# ET2_test_Chip_V1.net
KiCad netlist of a schematic drawn in Altium Designer
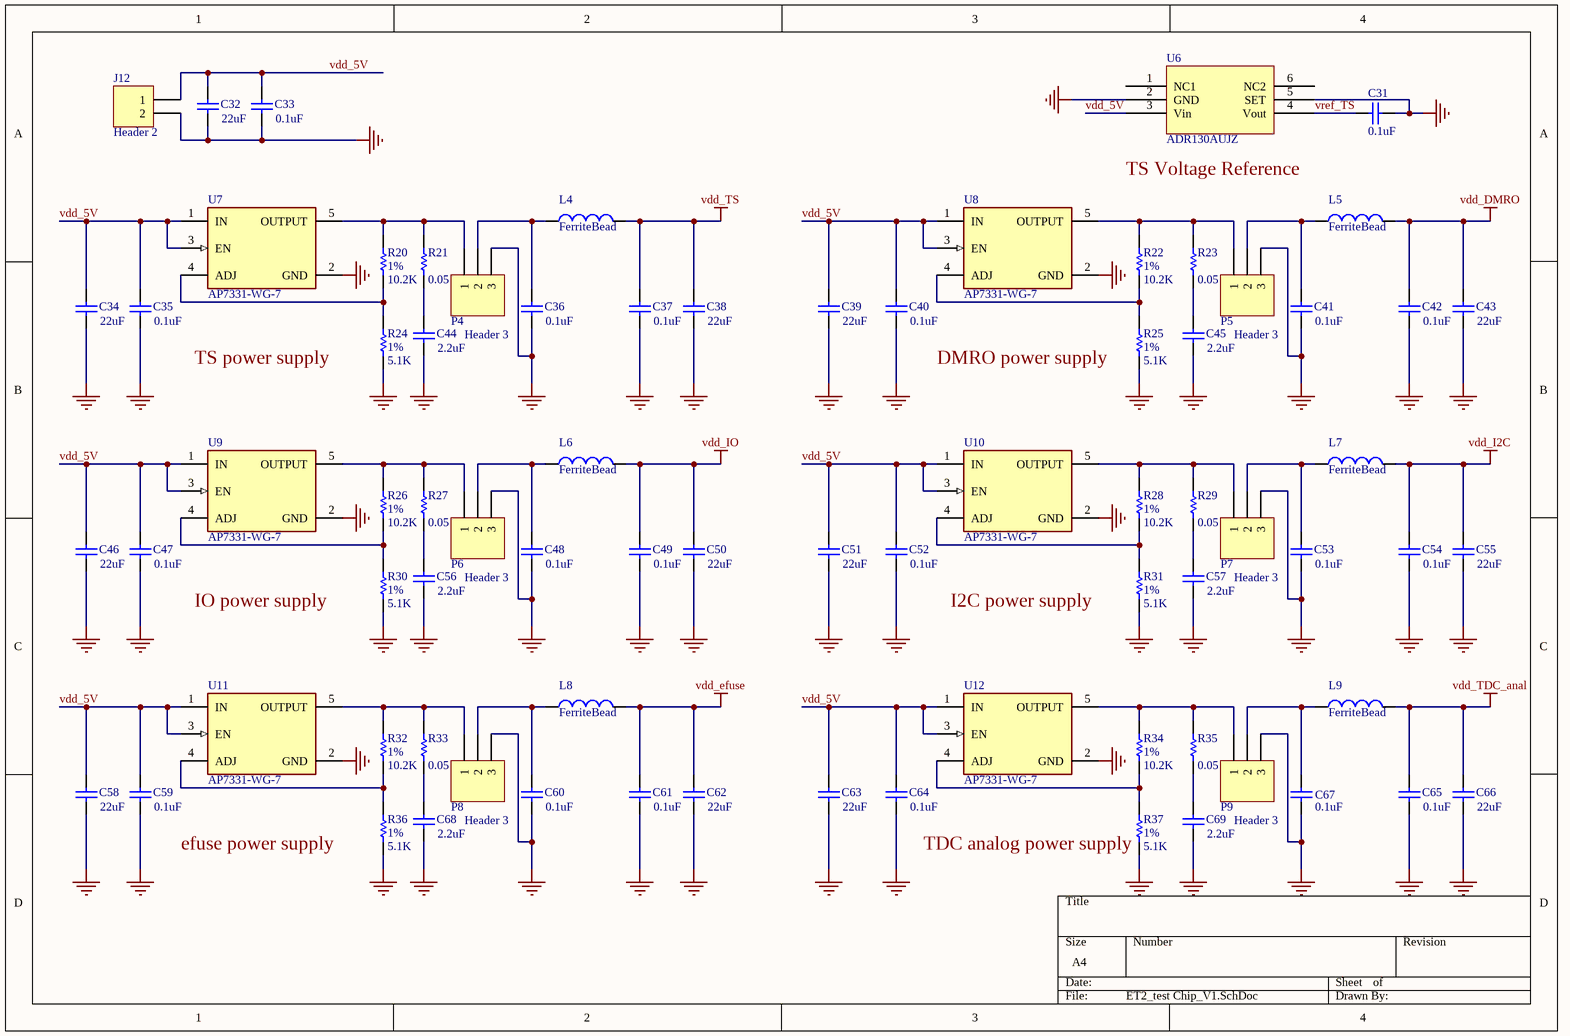
[diagram p0: ET2_test Chip_V1.SchDoc]

(export (version "E")
  (design (tool "Eeschema 10.0.6"))
  (components
    (comp (ref "C31")
      (value "0.1uF")
      (footprint "0402-eagle")
      (description "Capacitor")
      (fields (field (name "Comment") "Cap") (field (name "PUBLISHER") "Altium Limited"))
      (libsource (lib "Miscellaneous Devices") (part "Cap"))
    )
    (comp (ref "C32")
      (value "22uF")
      (footprint "C1210")
      (description "Capacitor")
      (fields (field (name "Comment") "Cap") (field (name "PUBLISHER") "Altium Limited"))
      (libsource (lib "Miscellaneous Devices") (part "Cap"))
    )
    (comp (ref "C33")
      (value "0.1uF")
      (footprint "0805-eagle")
      (description "Capacitor")
      (fields (field (name "Comment") "Cap") (field (name "PUBLISHER") "Altium Limited"))
      (libsource (lib "Miscellaneous Devices") (part "Cap"))
    )
    (comp (ref "C34")
      (value "22uF")
      (footprint "C1210")
      (description "Capacitor")
      (fields (field (name "Comment") "Cap") (field (name "PUBLISHER") "Altium Limited"))
      (libsource (lib "Miscellaneous Devices") (part "Cap"))
    )
    (comp (ref "C35")
      (value "0.1uF")
      (footprint "0805-eagle")
      (description "Capacitor")
      (fields (field (name "Comment") "Cap") (field (name "PUBLISHER") "Altium Limited"))
      (libsource (lib "Miscellaneous Devices") (part "Cap"))
    )
    (comp (ref "C36")
      (value "0.1uF")
      (footprint "0805-eagle")
      (description "Capacitor")
      (fields (field (name "Comment") "Cap") (field (name "PUBLISHER") "Altium Limited"))
      (libsource (lib "Miscellaneous Devices") (part "Cap"))
    )
    (comp (ref "C37")
      (value "0.1uF")
      (footprint "0805-eagle")
      (description "Capacitor")
      (fields (field (name "Comment") "Cap") (field (name "PUBLISHER") "Altium Limited"))
      (libsource (lib "Miscellaneous Devices") (part "Cap"))
    )
    (comp (ref "C38")
      (value "22uF")
      (footprint "C1210")
      (description "Capacitor")
      (fields (field (name "Comment") "Cap") (field (name "PUBLISHER") "Altium Limited"))
      (libsource (lib "Miscellaneous Devices") (part "Cap"))
    )
    (comp (ref "C39")
      (value "22uF")
      (footprint "C1210")
      (description "Capacitor")
      (fields (field (name "Comment") "Cap") (field (name "PUBLISHER") "Altium Limited"))
      (libsource (lib "Miscellaneous Devices") (part "Cap"))
    )
    (comp (ref "C40")
      (value "0.1uF")
      (footprint "0805-eagle")
      (description "Capacitor")
      (fields (field (name "Comment") "Cap") (field (name "PUBLISHER") "Altium Limited"))
      (libsource (lib "Miscellaneous Devices") (part "Cap"))
    )
    (comp (ref "C41")
      (value "0.1uF")
      (footprint "0805-eagle")
      (description "Capacitor")
      (fields (field (name "Comment") "Cap") (field (name "PUBLISHER") "Altium Limited"))
      (libsource (lib "Miscellaneous Devices") (part "Cap"))
    )
    (comp (ref "C42")
      (value "0.1uF")
      (footprint "0805-eagle")
      (description "Capacitor")
      (fields (field (name "Comment") "Cap") (field (name "PUBLISHER") "Altium Limited"))
      (libsource (lib "Miscellaneous Devices") (part "Cap"))
    )
    (comp (ref "C43")
      (value "22uF")
      (footprint "C1210")
      (description "Capacitor")
      (fields (field (name "Comment") "Cap") (field (name "PUBLISHER") "Altium Limited"))
      (libsource (lib "Miscellaneous Devices") (part "Cap"))
    )
    (comp (ref "C44")
      (value "2.2uF")
      (footprint "0805-eagle")
      (description "Capacitor")
      (fields (field (name "Comment") "Cap") (field (name "PUBLISHER") "Altium Limited"))
      (libsource (lib "Miscellaneous Devices") (part "Cap"))
    )
    (comp (ref "C45")
      (value "2.2uF")
      (footprint "0805-eagle")
      (description "Capacitor")
      (fields (field (name "Comment") "Cap") (field (name "PUBLISHER") "Altium Limited"))
      (libsource (lib "Miscellaneous Devices") (part "Cap"))
    )
    (comp (ref "C46")
      (value "22uF")
      (footprint "C1210")
      (description "Capacitor")
      (fields (field (name "Comment") "Cap") (field (name "PUBLISHER") "Altium Limited"))
      (libsource (lib "Miscellaneous Devices") (part "Cap"))
    )
    (comp (ref "C47")
      (value "0.1uF")
      (footprint "0805-eagle")
      (description "Capacitor")
      (fields (field (name "Comment") "Cap") (field (name "PUBLISHER") "Altium Limited"))
      (libsource (lib "Miscellaneous Devices") (part "Cap"))
    )
    (comp (ref "C48")
      (value "0.1uF")
      (footprint "0805-eagle")
      (description "Capacitor")
      (fields (field (name "Comment") "Cap") (field (name "PUBLISHER") "Altium Limited"))
      (libsource (lib "Miscellaneous Devices") (part "Cap"))
    )
    (comp (ref "C49")
      (value "0.1uF")
      (footprint "0805-eagle")
      (description "Capacitor")
      (fields (field (name "Comment") "Cap") (field (name "PUBLISHER") "Altium Limited"))
      (libsource (lib "Miscellaneous Devices") (part "Cap"))
    )
    (comp (ref "C50")
      (value "22uF")
      (footprint "C1210")
      (description "Capacitor")
      (fields (field (name "Comment") "Cap") (field (name "PUBLISHER") "Altium Limited"))
      (libsource (lib "Miscellaneous Devices") (part "Cap"))
    )
    (comp (ref "C51")
      (value "22uF")
      (footprint "C1210")
      (description "Capacitor")
      (fields (field (name "Comment") "Cap") (field (name "PUBLISHER") "Altium Limited"))
      (libsource (lib "Miscellaneous Devices") (part "Cap"))
    )
    (comp (ref "C52")
      (value "0.1uF")
      (footprint "0805-eagle")
      (description "Capacitor")
      (fields (field (name "Comment") "Cap") (field (name "PUBLISHER") "Altium Limited"))
      (libsource (lib "Miscellaneous Devices") (part "Cap"))
    )
    (comp (ref "C53")
      (value "0.1uF")
      (footprint "0805-eagle")
      (description "Capacitor")
      (fields (field (name "Comment") "Cap") (field (name "PUBLISHER") "Altium Limited"))
      (libsource (lib "Miscellaneous Devices") (part "Cap"))
    )
    (comp (ref "C54")
      (value "0.1uF")
      (footprint "0805-eagle")
      (description "Capacitor")
      (fields (field (name "Comment") "Cap") (field (name "PUBLISHER") "Altium Limited"))
      (libsource (lib "Miscellaneous Devices") (part "Cap"))
    )
    (comp (ref "C55")
      (value "22uF")
      (footprint "C1210")
      (description "Capacitor")
      (fields (field (name "Comment") "Cap") (field (name "PUBLISHER") "Altium Limited"))
      (libsource (lib "Miscellaneous Devices") (part "Cap"))
    )
    (comp (ref "C56")
      (value "2.2uF")
      (footprint "0805-eagle")
      (description "Capacitor")
      (fields (field (name "Comment") "Cap") (field (name "PUBLISHER") "Altium Limited"))
      (libsource (lib "Miscellaneous Devices") (part "Cap"))
    )
    (comp (ref "C57")
      (value "2.2uF")
      (footprint "0805-eagle")
      (description "Capacitor")
      (fields (field (name "Comment") "Cap") (field (name "PUBLISHER") "Altium Limited"))
      (libsource (lib "Miscellaneous Devices") (part "Cap"))
    )
    (comp (ref "C58")
      (value "22uF")
      (footprint "C1210")
      (description "Capacitor")
      (fields (field (name "Comment") "Cap") (field (name "PUBLISHER") "Altium Limited"))
      (libsource (lib "Miscellaneous Devices") (part "Cap"))
    )
    (comp (ref "C59")
      (value "0.1uF")
      (footprint "0805-eagle")
      (description "Capacitor")
      (fields (field (name "Comment") "Cap") (field (name "PUBLISHER") "Altium Limited"))
      (libsource (lib "Miscellaneous Devices") (part "Cap"))
    )
    (comp (ref "C60")
      (value "0.1uF")
      (footprint "0805-eagle")
      (description "Capacitor")
      (fields (field (name "Comment") "Cap") (field (name "PUBLISHER") "Altium Limited"))
      (libsource (lib "Miscellaneous Devices") (part "Cap"))
    )
    (comp (ref "C61")
      (value "0.1uF")
      (footprint "0805-eagle")
      (description "Capacitor")
      (fields (field (name "Comment") "Cap") (field (name "PUBLISHER") "Altium Limited"))
      (libsource (lib "Miscellaneous Devices") (part "Cap"))
    )
    (comp (ref "C62")
      (value "22uF")
      (footprint "C1210")
      (description "Capacitor")
      (fields (field (name "Comment") "Cap") (field (name "PUBLISHER") "Altium Limited"))
      (libsource (lib "Miscellaneous Devices") (part "Cap"))
    )
    (comp (ref "C63")
      (value "22uF")
      (footprint "C1210")
      (description "Capacitor")
      (fields (field (name "Comment") "Cap") (field (name "PUBLISHER") "Altium Limited"))
      (libsource (lib "Miscellaneous Devices") (part "Cap"))
    )
    (comp (ref "C64")
      (value "0.1uF")
      (footprint "0805-eagle")
      (description "Capacitor")
      (fields (field (name "Comment") "Cap") (field (name "PUBLISHER") "Altium Limited"))
      (libsource (lib "Miscellaneous Devices") (part "Cap"))
    )
    (comp (ref "C65")
      (value "0.1uF")
      (footprint "0805-eagle")
      (description "Capacitor")
      (fields (field (name "Comment") "Cap") (field (name "PUBLISHER") "Altium Limited"))
      (libsource (lib "Miscellaneous Devices") (part "Cap"))
    )
    (comp (ref "C66")
      (value "22uF")
      (footprint "C1210")
      (description "Capacitor")
      (fields (field (name "Comment") "Cap") (field (name "PUBLISHER") "Altium Limited"))
      (libsource (lib "Miscellaneous Devices") (part "Cap"))
    )
    (comp (ref "C67")
      (value "0.1uF")
      (footprint "0805-eagle")
      (description "Capacitor")
      (fields (field (name "Comment") "Cap") (field (name "PUBLISHER") "Altium Limited"))
      (libsource (lib "Miscellaneous Devices") (part "Cap"))
    )
    (comp (ref "C68")
      (value "2.2uF")
      (footprint "0805-eagle")
      (description "Capacitor")
      (fields (field (name "Comment") "Cap") (field (name "PUBLISHER") "Altium Limited"))
      (libsource (lib "Miscellaneous Devices") (part "Cap"))
    )
    (comp (ref "C69")
      (value "2.2uF")
      (footprint "0805-eagle")
      (description "Capacitor")
      (fields (field (name "Comment") "Cap") (field (name "PUBLISHER") "Altium Limited"))
      (libsource (lib "Miscellaneous Devices") (part "Cap"))
    )
    (comp (ref "J12")
      (value "Header 2")
      (footprint "PowerJ2")
      (description "Header, 2-Pin")
      (fields (field (name "PUBLISHER") "Altium Limited"))
      (libsource (lib "Miscellaneous Connectors") (part "Header 2"))
    )
    (comp (ref "L4")
      (value "FerriteBead")
      (footprint "0805-eagle")
      (description "Inductor")
      (fields (field (name "PUBLISHER") "Altium Limited"))
      (libsource (lib "Miscellaneous Devices") (part "Inductor"))
    )
    (comp (ref "L5")
      (value "FerriteBead")
      (footprint "0805-eagle")
      (description "Inductor")
      (fields (field (name "PUBLISHER") "Altium Limited"))
      (libsource (lib "Miscellaneous Devices") (part "Inductor"))
    )
    (comp (ref "L6")
      (value "FerriteBead")
      (footprint "0805-eagle")
      (description "Inductor")
      (fields (field (name "PUBLISHER") "Altium Limited"))
      (libsource (lib "Miscellaneous Devices") (part "Inductor"))
    )
    (comp (ref "L7")
      (value "FerriteBead")
      (footprint "0805-eagle")
      (description "Inductor")
      (fields (field (name "PUBLISHER") "Altium Limited"))
      (libsource (lib "Miscellaneous Devices") (part "Inductor"))
    )
    (comp (ref "L8")
      (value "FerriteBead")
      (footprint "0805-eagle")
      (description "Inductor")
      (fields (field (name "PUBLISHER") "Altium Limited"))
      (libsource (lib "Miscellaneous Devices") (part "Inductor"))
    )
    (comp (ref "L9")
      (value "FerriteBead")
      (footprint "0805-eagle")
      (description "Inductor")
      (fields (field (name "PUBLISHER") "Altium Limited"))
      (libsource (lib "Miscellaneous Devices") (part "Inductor"))
    )
    (comp (ref "P4")
      (value "Header 3")
      (footprint "Header3_L")
      (description "Header, 3-Pin")
      (fields (field (name "PUBLISHER") "Altium Limited"))
      (libsource (lib "Miscellaneous Connectors") (part "Header 3"))
    )
    (comp (ref "P5")
      (value "Header 3")
      (footprint "Header3_L")
      (description "Header, 3-Pin")
      (fields (field (name "PUBLISHER") "Altium Limited"))
      (libsource (lib "Miscellaneous Connectors") (part "Header 3"))
    )
    (comp (ref "P6")
      (value "Header 3")
      (footprint "Header3_L")
      (description "Header, 3-Pin")
      (fields (field (name "PUBLISHER") "Altium Limited"))
      (libsource (lib "Miscellaneous Connectors") (part "Header 3"))
    )
    (comp (ref "P7")
      (value "Header 3")
      (footprint "Header3_L")
      (description "Header, 3-Pin")
      (fields (field (name "PUBLISHER") "Altium Limited"))
      (libsource (lib "Miscellaneous Connectors") (part "Header 3"))
    )
    (comp (ref "P8")
      (value "Header 3")
      (footprint "Header3_L")
      (description "Header, 3-Pin")
      (fields (field (name "PUBLISHER") "Altium Limited"))
      (libsource (lib "Miscellaneous Connectors") (part "Header 3"))
    )
    (comp (ref "P9")
      (value "Header 3")
      (footprint "Header3_L")
      (description "Header, 3-Pin")
      (fields (field (name "PUBLISHER") "Altium Limited"))
      (libsource (lib "Miscellaneous Connectors") (part "Header 3"))
    )
    (comp (ref "R20")
      (value "1%")
      (footprint "0402-eagle")
      (description "Resistor")
      (fields (field (name "ALTIUM_VALUE") "10.2K") (field (name "PUBLISHER") "Altium Limited"))
      (libsource (lib "Miscellaneous Devices") (part "Res1"))
    )
    (comp (ref "R21")
      (value "0.05")
      (footprint "0402-eagle")
      (description "Resistor")
      (fields (field (name "Comment") "1%") (field (name "PUBLISHER") "Altium Limited"))
      (libsource (lib "Miscellaneous Devices") (part "Res1"))
    )
    (comp (ref "R22")
      (value "1%")
      (footprint "0402-eagle")
      (description "Resistor")
      (fields (field (name "ALTIUM_VALUE") "10.2K") (field (name "PUBLISHER") "Altium Limited"))
      (libsource (lib "Miscellaneous Devices") (part "Res1"))
    )
    (comp (ref "R23")
      (value "0.05")
      (footprint "0402-eagle")
      (description "Resistor")
      (fields (field (name "Comment") "1%") (field (name "PUBLISHER") "Altium Limited"))
      (libsource (lib "Miscellaneous Devices") (part "Res1"))
    )
    (comp (ref "R24")
      (value "1%")
      (footprint "0402-eagle")
      (description "Resistor")
      (fields (field (name "ALTIUM_VALUE") "5.1K") (field (name "PUBLISHER") "Altium Limited"))
      (libsource (lib "Miscellaneous Devices") (part "Res1"))
    )
    (comp (ref "R25")
      (value "1%")
      (footprint "0402-eagle")
      (description "Resistor")
      (fields (field (name "ALTIUM_VALUE") "5.1K") (field (name "PUBLISHER") "Altium Limited"))
      (libsource (lib "Miscellaneous Devices") (part "Res1"))
    )
    (comp (ref "R26")
      (value "1%")
      (footprint "0402-eagle")
      (description "Resistor")
      (fields (field (name "ALTIUM_VALUE") "10.2K") (field (name "PUBLISHER") "Altium Limited"))
      (libsource (lib "Miscellaneous Devices") (part "Res1"))
    )
    (comp (ref "R27")
      (value "0.05")
      (footprint "0402-eagle")
      (description "Resistor")
      (fields (field (name "Comment") "1%") (field (name "PUBLISHER") "Altium Limited"))
      (libsource (lib "Miscellaneous Devices") (part "Res1"))
    )
    (comp (ref "R28")
      (value "1%")
      (footprint "0402-eagle")
      (description "Resistor")
      (fields (field (name "ALTIUM_VALUE") "10.2K") (field (name "PUBLISHER") "Altium Limited"))
      (libsource (lib "Miscellaneous Devices") (part "Res1"))
    )
    (comp (ref "R29")
      (value "0.05")
      (footprint "0402-eagle")
      (description "Resistor")
      (fields (field (name "Comment") "1%") (field (name "PUBLISHER") "Altium Limited"))
      (libsource (lib "Miscellaneous Devices") (part "Res1"))
    )
    (comp (ref "R30")
      (value "1%")
      (footprint "0402-eagle")
      (description "Resistor")
      (fields (field (name "ALTIUM_VALUE") "5.1K") (field (name "PUBLISHER") "Altium Limited"))
      (libsource (lib "Miscellaneous Devices") (part "Res1"))
    )
    (comp (ref "R31")
      (value "1%")
      (footprint "0402-eagle")
      (description "Resistor")
      (fields (field (name "ALTIUM_VALUE") "5.1K") (field (name "PUBLISHER") "Altium Limited"))
      (libsource (lib "Miscellaneous Devices") (part "Res1"))
    )
    (comp (ref "R32")
      (value "1%")
      (footprint "0402-eagle")
      (description "Resistor")
      (fields (field (name "ALTIUM_VALUE") "10.2K") (field (name "PUBLISHER") "Altium Limited"))
      (libsource (lib "Miscellaneous Devices") (part "Res1"))
    )
    (comp (ref "R33")
      (value "0.05")
      (footprint "0402-eagle")
      (description "Resistor")
      (fields (field (name "Comment") "1%") (field (name "PUBLISHER") "Altium Limited"))
      (libsource (lib "Miscellaneous Devices") (part "Res1"))
    )
    (comp (ref "R34")
      (value "1%")
      (footprint "0402-eagle")
      (description "Resistor")
      (fields (field (name "ALTIUM_VALUE") "10.2K") (field (name "PUBLISHER") "Altium Limited"))
      (libsource (lib "Miscellaneous Devices") (part "Res1"))
    )
    (comp (ref "R35")
      (value "0.05")
      (footprint "0402-eagle")
      (description "Resistor")
      (fields (field (name "Comment") "1%") (field (name "PUBLISHER") "Altium Limited"))
      (libsource (lib "Miscellaneous Devices") (part "Res1"))
    )
    (comp (ref "R36")
      (value "1%")
      (footprint "0402-eagle")
      (description "Resistor")
      (fields (field (name "ALTIUM_VALUE") "5.1K") (field (name "PUBLISHER") "Altium Limited"))
      (libsource (lib "Miscellaneous Devices") (part "Res1"))
    )
    (comp (ref "R37")
      (value "1%")
      (footprint "0402-eagle")
      (description "Resistor")
      (fields (field (name "ALTIUM_VALUE") "5.1K") (field (name "PUBLISHER") "Altium Limited"))
      (libsource (lib "Miscellaneous Devices") (part "Res1"))
    )
    (comp (ref "U6") (value "ADR130AUJZ") (footprint "ADR130") (libsource (lib "MySchLib") (part "ADR130")))
    (comp (ref "U7")
      (value "AP7331-WG-7")
      (footprint "FP-SOT25-MFG")
      (description "IC REG LIN POS ADJ 300MA SOT25")
      (fields
        (field (name "OCTOPART") "https://octopart.com/ap7331-wg-7-diodes+inc.-17930424")
        (field (name "MANUFACTURER") "Diodes Inc.")
      )
      (libsource (lib "MySchLib") (part "CMP-12756-000022-1"))
    )
    (comp (ref "U8")
      (value "AP7331-WG-7")
      (footprint "FP-SOT25-MFG")
      (description "IC REG LIN POS ADJ 300MA SOT25")
      (fields
        (field (name "OCTOPART") "https://octopart.com/ap7331-wg-7-diodes+inc.-17930424")
        (field (name "MANUFACTURER") "Diodes Inc.")
      )
      (libsource (lib "MySchLib") (part "CMP-12756-000022-1"))
    )
    (comp (ref "U9")
      (value "AP7331-WG-7")
      (footprint "FP-SOT25-MFG")
      (description "IC REG LIN POS ADJ 300MA SOT25")
      (fields
        (field (name "OCTOPART") "https://octopart.com/ap7331-wg-7-diodes+inc.-17930424")
        (field (name "MANUFACTURER") "Diodes Inc.")
      )
      (libsource (lib "MySchLib") (part "CMP-12756-000022-1"))
    )
    (comp (ref "U10")
      (value "AP7331-WG-7")
      (footprint "FP-SOT25-MFG")
      (description "IC REG LIN POS ADJ 300MA SOT25")
      (fields
        (field (name "OCTOPART") "https://octopart.com/ap7331-wg-7-diodes+inc.-17930424")
        (field (name "MANUFACTURER") "Diodes Inc.")
      )
      (libsource (lib "MySchLib") (part "CMP-12756-000022-1"))
    )
    (comp (ref "U11")
      (value "AP7331-WG-7")
      (footprint "FP-SOT25-MFG")
      (description "IC REG LIN POS ADJ 300MA SOT25")
      (fields
        (field (name "OCTOPART") "https://octopart.com/ap7331-wg-7-diodes+inc.-17930424")
        (field (name "MANUFACTURER") "Diodes Inc.")
      )
      (libsource (lib "MySchLib") (part "CMP-12756-000022-1"))
    )
    (comp (ref "U12")
      (value "AP7331-WG-7")
      (footprint "FP-SOT25-MFG")
      (description "IC REG LIN POS ADJ 300MA SOT25")
      (fields
        (field (name "OCTOPART") "https://octopart.com/ap7331-wg-7-diodes+inc.-17930424")
        (field (name "MANUFACTURER") "Diodes Inc.")
      )
      (libsource (lib "MySchLib") (part "CMP-12756-000022-1"))
    )
  )
  (nets
    (net (code "1") (name "/vdd_5V") (class "Default")
      (node (ref "C32") (pin "2") (pinfunction "2_2") (pintype "passive"))
      (node (ref "C33") (pin "2") (pinfunction "2_2") (pintype "passive"))
      (node (ref "C34") (pin "2") (pinfunction "2_2") (pintype "passive"))
      (node (ref "C35") (pin "2") (pinfunction "2_2") (pintype "passive"))
      (node (ref "C39") (pin "2") (pinfunction "2_2") (pintype "passive"))
      (node (ref "C40") (pin "2") (pinfunction "2_2") (pintype "passive"))
      (node (ref "C46") (pin "2") (pinfunction "2_2") (pintype "passive"))
      (node (ref "C47") (pin "2") (pinfunction "2_2") (pintype "passive"))
      (node (ref "C51") (pin "2") (pinfunction "2_2") (pintype "passive"))
      (node (ref "C52") (pin "2") (pinfunction "2_2") (pintype "passive"))
      (node (ref "C58") (pin "2") (pinfunction "2_2") (pintype "passive"))
      (node (ref "C59") (pin "2") (pinfunction "2_2") (pintype "passive"))
      (node (ref "C63") (pin "2") (pinfunction "2_2") (pintype "passive"))
      (node (ref "C64") (pin "2") (pinfunction "2_2") (pintype "passive"))
      (node (ref "J12") (pin "1") (pinfunction "1_1") (pintype "passive"))
      (node (ref "U10") (pin "1") (pinfunction "IN_1") (pintype "power_in"))
      (node (ref "U10") (pin "3") (pinfunction "EN_3") (pintype "input"))
      (node (ref "U11") (pin "1") (pinfunction "IN_1") (pintype "power_in"))
      (node (ref "U11") (pin "3") (pinfunction "EN_3") (pintype "input"))
      (node (ref "U12") (pin "1") (pinfunction "IN_1") (pintype "power_in"))
      (node (ref "U12") (pin "3") (pinfunction "EN_3") (pintype "input"))
      (node (ref "U6") (pin "3") (pinfunction "Vin_3") (pintype "passive"))
      (node (ref "U7") (pin "1") (pinfunction "IN_1") (pintype "power_in"))
      (node (ref "U7") (pin "3") (pinfunction "EN_3") (pintype "input"))
      (node (ref "U8") (pin "1") (pinfunction "IN_1") (pintype "power_in"))
      (node (ref "U8") (pin "3") (pinfunction "EN_3") (pintype "input"))
      (node (ref "U9") (pin "1") (pinfunction "IN_1") (pintype "power_in"))
      (node (ref "U9") (pin "3") (pinfunction "EN_3") (pintype "input"))
    )
    (net (code "2") (name "/vref_TS") (class "Default")
      (node (ref "C31") (pin "2") (pinfunction "2_2") (pintype "passive"))
      (node (ref "U6") (pin "4") (pinfunction "Vout_4") (pintype "passive"))
    )
    (net (code "3") (name "GND") (class "Default")
      (node (ref "C31") (pin "1") (pinfunction "1_1") (pintype "passive"))
      (node (ref "C32") (pin "1") (pinfunction "1_1") (pintype "passive"))
      (node (ref "C33") (pin "1") (pinfunction "1_1") (pintype "passive"))
      (node (ref "C34") (pin "1") (pinfunction "1_1") (pintype "passive"))
      (node (ref "C35") (pin "1") (pinfunction "1_1") (pintype "passive"))
      (node (ref "C36") (pin "1") (pinfunction "1_1") (pintype "passive"))
      (node (ref "C37") (pin "1") (pinfunction "1_1") (pintype "passive"))
      (node (ref "C38") (pin "1") (pinfunction "1_1") (pintype "passive"))
      (node (ref "C39") (pin "1") (pinfunction "1_1") (pintype "passive"))
      (node (ref "C40") (pin "1") (pinfunction "1_1") (pintype "passive"))
      (node (ref "C41") (pin "1") (pinfunction "1_1") (pintype "passive"))
      (node (ref "C42") (pin "1") (pinfunction "1_1") (pintype "passive"))
      (node (ref "C43") (pin "1") (pinfunction "1_1") (pintype "passive"))
      (node (ref "C44") (pin "1") (pinfunction "1_1") (pintype "passive"))
      (node (ref "C45") (pin "1") (pinfunction "1_1") (pintype "passive"))
      (node (ref "C46") (pin "1") (pinfunction "1_1") (pintype "passive"))
      (node (ref "C47") (pin "1") (pinfunction "1_1") (pintype "passive"))
      (node (ref "C48") (pin "1") (pinfunction "1_1") (pintype "passive"))
      (node (ref "C49") (pin "1") (pinfunction "1_1") (pintype "passive"))
      (node (ref "C50") (pin "1") (pinfunction "1_1") (pintype "passive"))
      (node (ref "C51") (pin "1") (pinfunction "1_1") (pintype "passive"))
      (node (ref "C52") (pin "1") (pinfunction "1_1") (pintype "passive"))
      (node (ref "C53") (pin "1") (pinfunction "1_1") (pintype "passive"))
      (node (ref "C54") (pin "1") (pinfunction "1_1") (pintype "passive"))
      (node (ref "C55") (pin "1") (pinfunction "1_1") (pintype "passive"))
      (node (ref "C56") (pin "1") (pinfunction "1_1") (pintype "passive"))
      (node (ref "C57") (pin "1") (pinfunction "1_1") (pintype "passive"))
      (node (ref "C58") (pin "1") (pinfunction "1_1") (pintype "passive"))
      (node (ref "C59") (pin "1") (pinfunction "1_1") (pintype "passive"))
      (node (ref "C60") (pin "1") (pinfunction "1_1") (pintype "passive"))
      (node (ref "C61") (pin "1") (pinfunction "1_1") (pintype "passive"))
      (node (ref "C62") (pin "1") (pinfunction "1_1") (pintype "passive"))
      (node (ref "C63") (pin "1") (pinfunction "1_1") (pintype "passive"))
      (node (ref "C64") (pin "1") (pinfunction "1_1") (pintype "passive"))
      (node (ref "C65") (pin "1") (pinfunction "1_1") (pintype "passive"))
      (node (ref "C66") (pin "1") (pinfunction "1_1") (pintype "passive"))
      (node (ref "C67") (pin "1") (pinfunction "1_1") (pintype "passive"))
      (node (ref "C68") (pin "1") (pinfunction "1_1") (pintype "passive"))
      (node (ref "C69") (pin "1") (pinfunction "1_1") (pintype "passive"))
      (node (ref "J12") (pin "2") (pinfunction "2_2") (pintype "passive"))
      (node (ref "P4") (pin "3") (pinfunction "3_3") (pintype "passive"))
      (node (ref "P5") (pin "3") (pinfunction "3_3") (pintype "passive"))
      (node (ref "P6") (pin "3") (pinfunction "3_3") (pintype "passive"))
      (node (ref "P7") (pin "3") (pinfunction "3_3") (pintype "passive"))
      (node (ref "P8") (pin "3") (pinfunction "3_3") (pintype "passive"))
      (node (ref "P9") (pin "3") (pinfunction "3_3") (pintype "passive"))
      (node (ref "R24") (pin "1") (pinfunction "1_1") (pintype "passive"))
      (node (ref "R25") (pin "1") (pinfunction "1_1") (pintype "passive"))
      (node (ref "R30") (pin "1") (pinfunction "1_1") (pintype "passive"))
      (node (ref "R31") (pin "1") (pinfunction "1_1") (pintype "passive"))
      (node (ref "R36") (pin "1") (pinfunction "1_1") (pintype "passive"))
      (node (ref "R37") (pin "1") (pinfunction "1_1") (pintype "passive"))
      (node (ref "U10") (pin "2") (pinfunction "GND_2") (pintype "power_in"))
      (node (ref "U11") (pin "2") (pinfunction "GND_2") (pintype "power_in"))
      (node (ref "U12") (pin "2") (pinfunction "GND_2") (pintype "power_in"))
      (node (ref "U6") (pin "2") (pinfunction "GND_2") (pintype "passive"))
      (node (ref "U6") (pin "5") (pinfunction "SET_5") (pintype "passive"))
      (node (ref "U7") (pin "2") (pinfunction "GND_2") (pintype "power_in"))
      (node (ref "U8") (pin "2") (pinfunction "GND_2") (pintype "power_in"))
      (node (ref "U9") (pin "2") (pinfunction "GND_2") (pintype "power_in"))
    )
    (net (code "4") (name "Net-(C36-Pad2)") (class "Default")
      (node (ref "C36") (pin "2") (pinfunction "2_2") (pintype "passive"))
      (node (ref "L4") (pin "1") (pinfunction "1_1") (pintype "passive"))
      (node (ref "P4") (pin "2") (pinfunction "2_2") (pintype "passive"))
    )
    (net (code "5") (name "Net-(C41-Pad2)") (class "Default")
      (node (ref "C41") (pin "2") (pinfunction "2_2") (pintype "passive"))
      (node (ref "L5") (pin "1") (pinfunction "1_1") (pintype "passive"))
      (node (ref "P5") (pin "2") (pinfunction "2_2") (pintype "passive"))
    )
    (net (code "6") (name "Net-(C44-Pad2)") (class "Default")
      (node (ref "C44") (pin "2") (pinfunction "2_2") (pintype "passive"))
      (node (ref "R21") (pin "1") (pinfunction "1_1") (pintype "passive"))
    )
    (net (code "7") (name "Net-(C45-Pad2)") (class "Default")
      (node (ref "C45") (pin "2") (pinfunction "2_2") (pintype "passive"))
      (node (ref "R23") (pin "1") (pinfunction "1_1") (pintype "passive"))
    )
    (net (code "8") (name "Net-(C48-Pad2)") (class "Default")
      (node (ref "C48") (pin "2") (pinfunction "2_2") (pintype "passive"))
      (node (ref "L6") (pin "1") (pinfunction "1_1") (pintype "passive"))
      (node (ref "P6") (pin "2") (pinfunction "2_2") (pintype "passive"))
    )
    (net (code "9") (name "Net-(C53-Pad2)") (class "Default")
      (node (ref "C53") (pin "2") (pinfunction "2_2") (pintype "passive"))
      (node (ref "L7") (pin "1") (pinfunction "1_1") (pintype "passive"))
      (node (ref "P7") (pin "2") (pinfunction "2_2") (pintype "passive"))
    )
    (net (code "10") (name "Net-(C56-Pad2)") (class "Default")
      (node (ref "C56") (pin "2") (pinfunction "2_2") (pintype "passive"))
      (node (ref "R27") (pin "1") (pinfunction "1_1") (pintype "passive"))
    )
    (net (code "11") (name "Net-(C57-Pad2)") (class "Default")
      (node (ref "C57") (pin "2") (pinfunction "2_2") (pintype "passive"))
      (node (ref "R29") (pin "1") (pinfunction "1_1") (pintype "passive"))
    )
    (net (code "12") (name "Net-(C60-Pad2)") (class "Default")
      (node (ref "C60") (pin "2") (pinfunction "2_2") (pintype "passive"))
      (node (ref "L8") (pin "1") (pinfunction "1_1") (pintype "passive"))
      (node (ref "P8") (pin "2") (pinfunction "2_2") (pintype "passive"))
    )
    (net (code "13") (name "Net-(C67-Pad2)") (class "Default")
      (node (ref "C67") (pin "2") (pinfunction "2_2") (pintype "passive"))
      (node (ref "L9") (pin "1") (pinfunction "1_1") (pintype "passive"))
      (node (ref "P9") (pin "2") (pinfunction "2_2") (pintype "passive"))
    )
    (net (code "14") (name "Net-(C68-Pad2)") (class "Default")
      (node (ref "C68") (pin "2") (pinfunction "2_2") (pintype "passive"))
      (node (ref "R33") (pin "1") (pinfunction "1_1") (pintype "passive"))
    )
    (net (code "15") (name "Net-(C69-Pad2)") (class "Default")
      (node (ref "C69") (pin "2") (pinfunction "2_2") (pintype "passive"))
      (node (ref "R35") (pin "1") (pinfunction "1_1") (pintype "passive"))
    )
    (net (code "16") (name "Net-(U7-ADJ)") (class "Default")
      (node (ref "R20") (pin "1") (pinfunction "1_1") (pintype "passive"))
      (node (ref "R24") (pin "2") (pinfunction "2_2") (pintype "passive"))
      (node (ref "U7") (pin "4") (pinfunction "ADJ_4") (pintype "passive"))
    )
    (net (code "17") (name "Net-(U7-OUTPUT)") (class "Default")
      (node (ref "P4") (pin "1") (pinfunction "1_1") (pintype "passive"))
      (node (ref "R20") (pin "2") (pinfunction "2_2") (pintype "passive"))
      (node (ref "R21") (pin "2") (pinfunction "2_2") (pintype "passive"))
      (node (ref "U7") (pin "5") (pinfunction "OUTPUT_5") (pintype "power_in"))
    )
    (net (code "18") (name "Net-(U8-ADJ)") (class "Default")
      (node (ref "R22") (pin "1") (pinfunction "1_1") (pintype "passive"))
      (node (ref "R25") (pin "2") (pinfunction "2_2") (pintype "passive"))
      (node (ref "U8") (pin "4") (pinfunction "ADJ_4") (pintype "passive"))
    )
    (net (code "19") (name "Net-(U8-OUTPUT)") (class "Default")
      (node (ref "P5") (pin "1") (pinfunction "1_1") (pintype "passive"))
      (node (ref "R22") (pin "2") (pinfunction "2_2") (pintype "passive"))
      (node (ref "R23") (pin "2") (pinfunction "2_2") (pintype "passive"))
      (node (ref "U8") (pin "5") (pinfunction "OUTPUT_5") (pintype "power_in"))
    )
    (net (code "20") (name "Net-(U9-ADJ)") (class "Default")
      (node (ref "R26") (pin "1") (pinfunction "1_1") (pintype "passive"))
      (node (ref "R30") (pin "2") (pinfunction "2_2") (pintype "passive"))
      (node (ref "U9") (pin "4") (pinfunction "ADJ_4") (pintype "passive"))
    )
    (net (code "21") (name "Net-(U9-OUTPUT)") (class "Default")
      (node (ref "P6") (pin "1") (pinfunction "1_1") (pintype "passive"))
      (node (ref "R26") (pin "2") (pinfunction "2_2") (pintype "passive"))
      (node (ref "R27") (pin "2") (pinfunction "2_2") (pintype "passive"))
      (node (ref "U9") (pin "5") (pinfunction "OUTPUT_5") (pintype "power_in"))
    )
    (net (code "22") (name "Net-(U10-ADJ)") (class "Default")
      (node (ref "R28") (pin "1") (pinfunction "1_1") (pintype "passive"))
      (node (ref "R31") (pin "2") (pinfunction "2_2") (pintype "passive"))
      (node (ref "U10") (pin "4") (pinfunction "ADJ_4") (pintype "passive"))
    )
    (net (code "23") (name "Net-(U10-OUTPUT)") (class "Default")
      (node (ref "P7") (pin "1") (pinfunction "1_1") (pintype "passive"))
      (node (ref "R28") (pin "2") (pinfunction "2_2") (pintype "passive"))
      (node (ref "R29") (pin "2") (pinfunction "2_2") (pintype "passive"))
      (node (ref "U10") (pin "5") (pinfunction "OUTPUT_5") (pintype "power_in"))
    )
    (net (code "24") (name "Net-(U11-ADJ)") (class "Default")
      (node (ref "R32") (pin "1") (pinfunction "1_1") (pintype "passive"))
      (node (ref "R36") (pin "2") (pinfunction "2_2") (pintype "passive"))
      (node (ref "U11") (pin "4") (pinfunction "ADJ_4") (pintype "passive"))
    )
    (net (code "25") (name "Net-(U11-OUTPUT)") (class "Default")
      (node (ref "P8") (pin "1") (pinfunction "1_1") (pintype "passive"))
      (node (ref "R32") (pin "2") (pinfunction "2_2") (pintype "passive"))
      (node (ref "R33") (pin "2") (pinfunction "2_2") (pintype "passive"))
      (node (ref "U11") (pin "5") (pinfunction "OUTPUT_5") (pintype "power_in"))
    )
    (net (code "26") (name "Net-(U12-ADJ)") (class "Default")
      (node (ref "R34") (pin "1") (pinfunction "1_1") (pintype "passive"))
      (node (ref "R37") (pin "2") (pinfunction "2_2") (pintype "passive"))
      (node (ref "U12") (pin "4") (pinfunction "ADJ_4") (pintype "passive"))
    )
    (net (code "27") (name "Net-(U12-OUTPUT)") (class "Default")
      (node (ref "P9") (pin "1") (pinfunction "1_1") (pintype "passive"))
      (node (ref "R34") (pin "2") (pinfunction "2_2") (pintype "passive"))
      (node (ref "R35") (pin "2") (pinfunction "2_2") (pintype "passive"))
      (node (ref "U12") (pin "5") (pinfunction "OUTPUT_5") (pintype "power_in"))
    )
    (net (code "28") (name "unconnected-(U6-NC1-Pad1)") (class "Default")
      (node (ref "U6") (pin "1") (pinfunction "NC1_1") (pintype "passive"))
    )
    (net (code "29") (name "unconnected-(U6-NC2-Pad6)") (class "Default")
      (node (ref "U6") (pin "6") (pinfunction "NC2_6") (pintype "passive"))
    )
    (net (code "30") (name "vdd_DMRO") (class "Default")
      (node (ref "C42") (pin "2") (pinfunction "2_2") (pintype "passive"))
      (node (ref "C43") (pin "2") (pinfunction "2_2") (pintype "passive"))
      (node (ref "L5") (pin "2") (pinfunction "2_2") (pintype "passive"))
    )
    (net (code "31") (name "vdd_I2C") (class "Default")
      (node (ref "C54") (pin "2") (pinfunction "2_2") (pintype "passive"))
      (node (ref "C55") (pin "2") (pinfunction "2_2") (pintype "passive"))
      (node (ref "L7") (pin "2") (pinfunction "2_2") (pintype "passive"))
    )
    (net (code "32") (name "vdd_IO") (class "Default")
      (node (ref "C49") (pin "2") (pinfunction "2_2") (pintype "passive"))
      (node (ref "C50") (pin "2") (pinfunction "2_2") (pintype "passive"))
      (node (ref "L6") (pin "2") (pinfunction "2_2") (pintype "passive"))
    )
    (net (code "33") (name "vdd_TDC_anal") (class "Default")
      (node (ref "C65") (pin "2") (pinfunction "2_2") (pintype "passive"))
      (node (ref "C66") (pin "2") (pinfunction "2_2") (pintype "passive"))
      (node (ref "L9") (pin "2") (pinfunction "2_2") (pintype "passive"))
    )
    (net (code "34") (name "vdd_TS") (class "Default")
      (node (ref "C37") (pin "2") (pinfunction "2_2") (pintype "passive"))
      (node (ref "C38") (pin "2") (pinfunction "2_2") (pintype "passive"))
      (node (ref "L4") (pin "2") (pinfunction "2_2") (pintype "passive"))
    )
    (net (code "35") (name "vdd_efuse") (class "Default")
      (node (ref "C61") (pin "2") (pinfunction "2_2") (pintype "passive"))
      (node (ref "C62") (pin "2") (pinfunction "2_2") (pintype "passive"))
      (node (ref "L8") (pin "2") (pinfunction "2_2") (pintype "passive"))
    )
  )
)
